# Microcontroller.net
KiCad netlist of a schematic drawn in Altium Designer
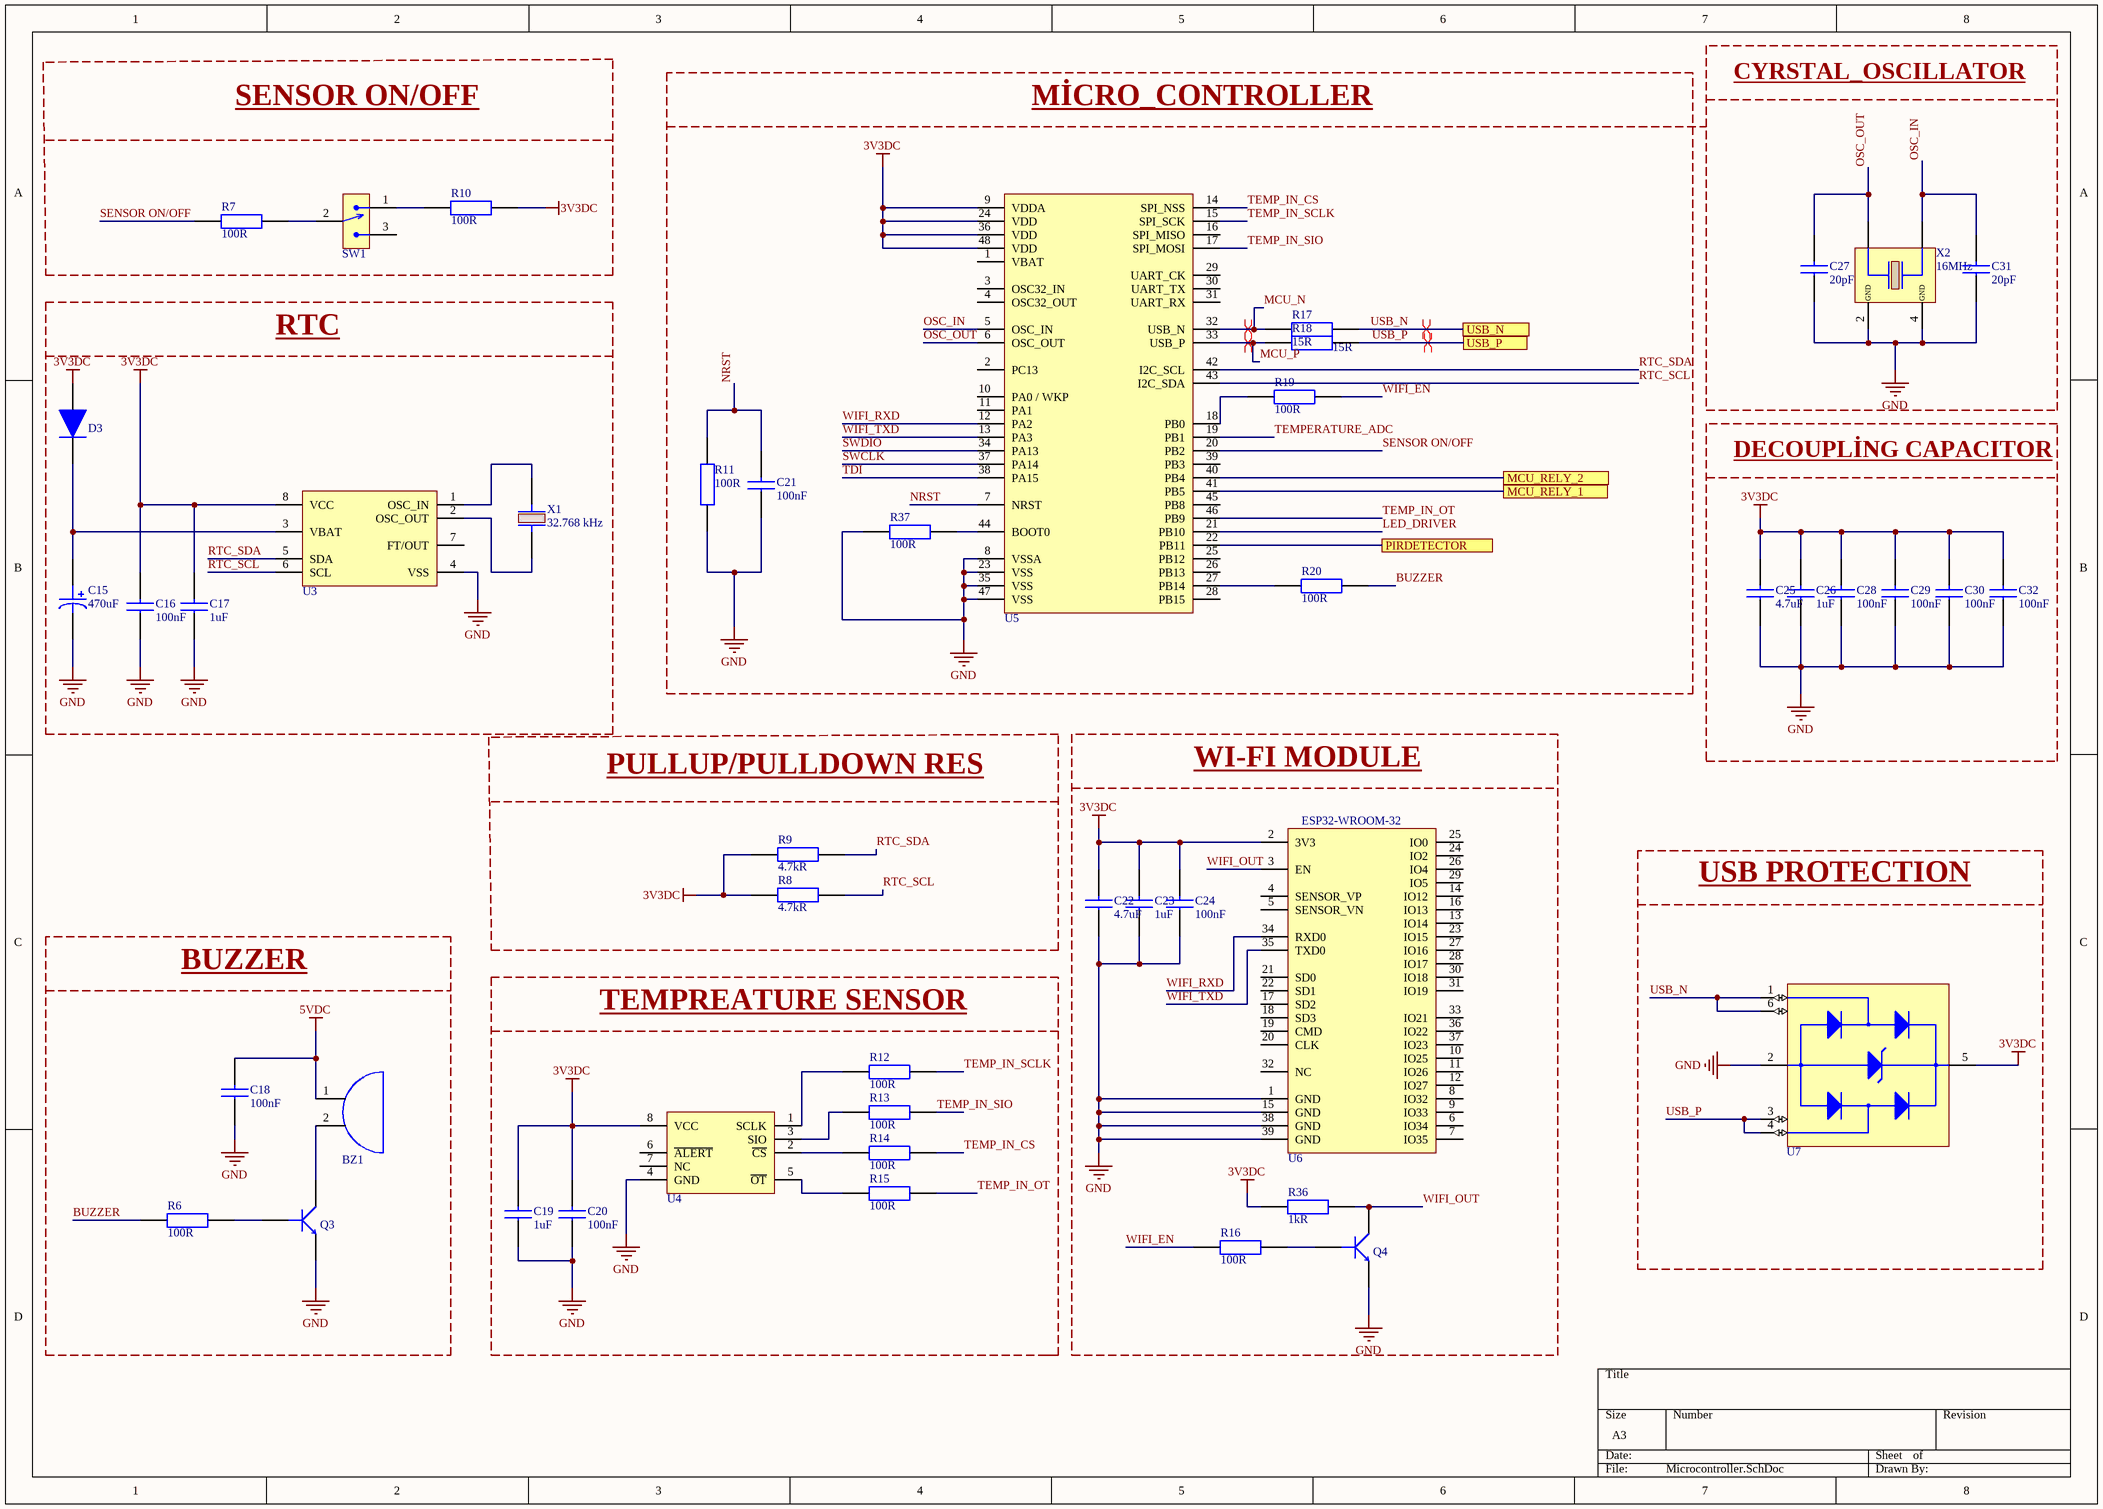
[diagram p0: Microcontroller.SchDoc]

(export (version "E")
  (design (tool "Eeschema 10.0.6"))
  (components
    (comp (ref "BZ1")
      (value "CMI-9605IC-0580T")
      (footprint "CMI-9605IC")
      (description "Buzzers Indicator, Internally Driven Magnetic 5V 30mA 2.7kHz 80dB @ 5V, 10cm Through Hole PC Pins")
      (fields (field (name "MANUFACTURER") "CUI Devices") (field (name "DESIGNED BY") "BERK"))
      (libsource (lib "UDEMY_Library") (part "CMI-9605IC-0580T"))
    )
    (comp (ref "C15")
      (value "ESH477M050AH4AA")
      (footprint "CAP_RADIAL_D10_P5")
      (description "CAP ALU ELEC 470uF 50V RADIAL")
      (fields
        (field (name "MANUFACTURER") "KEMET")
        (field (name "TOLERANCE") "20%")
        (field (name "CAPACITANCE") "470uF")
        (field (name "DESIGNED BY") "BERK")
      )
      (libsource (lib "UDEMY_Library") (part "CAP ALU ELEC 470uF 50V"))
    )
    (comp (ref "C16")
      (value "C0603C104K5RACTU")
      (footprint "CAP_0603")
      (description "CAP CER 100nF %10 0603 SMD")
      (fields
        (field (name "MANUFACTURER") "KEMET")
        (field (name "TOLERANCE") "10%")
        (field (name "CAPACITANCE") "100nF")
        (field (name "DESIGNED BY") "BERK")
      )
      (libsource (lib "UDEMY_Library") (part "CAP CER 100nF 0603"))
    )
    (comp (ref "C17")
      (value "CL21B105KBFNNNE")
      (footprint "CAP_0805")
      (description "CAP CER 1uF %10 0805")
      (fields
        (field (name "MANUFACTURER") "Samsung")
        (field (name "TOLERANCE") "10%")
        (field (name "CAPACITANCE") "1uF")
        (field (name "DESIGNED BY") "BERK")
      )
      (libsource (lib "UDEMY_Library") (part "CAP CER 1uF 0805"))
    )
    (comp (ref "C18")
      (value "C0603C104K5RACTU")
      (footprint "CAP_0603")
      (description "CAP CER 100nF %10 0603 SMD")
      (fields
        (field (name "MANUFACTURER") "KEMET")
        (field (name "TOLERANCE") "10%")
        (field (name "CAPACITANCE") "100nF")
        (field (name "DESIGNED BY") "BERK")
      )
      (libsource (lib "UDEMY_Library") (part "CAP CER 100nF 0603"))
    )
    (comp (ref "C19")
      (value "CL21B105KBFNNNE")
      (footprint "CAP_0805")
      (description "CAP CER 1uF %10 0805")
      (fields
        (field (name "MANUFACTURER") "Samsung")
        (field (name "TOLERANCE") "10%")
        (field (name "CAPACITANCE") "1uF")
        (field (name "DESIGNED BY") "BERK")
      )
      (libsource (lib "UDEMY_Library") (part "CAP CER 1uF 0805"))
    )
    (comp (ref "C20")
      (value "C0603C104K5RACTU")
      (footprint "CAP_0603")
      (description "CAP CER 100nF %10 0603 SMD")
      (fields
        (field (name "MANUFACTURER") "KEMET")
        (field (name "TOLERANCE") "10%")
        (field (name "CAPACITANCE") "100nF")
        (field (name "DESIGNED BY") "BERK")
      )
      (libsource (lib "UDEMY_Library") (part "CAP CER 100nF 0603"))
    )
    (comp (ref "C21")
      (value "C0603C104K5RACTU")
      (footprint "CAP_0603")
      (description "CAP CER 100nF %10 0603 SMD")
      (fields
        (field (name "MANUFACTURER") "KEMET")
        (field (name "TOLERANCE") "10%")
        (field (name "CAPACITANCE") "100nF")
        (field (name "DESIGNED BY") "BERK")
      )
      (libsource (lib "UDEMY_Library") (part "CAP CER 100nF 0603"))
    )
    (comp (ref "C22")
      (value "CL21A475KAQNNNE")
      (footprint "CAP_0805")
      (description "CAP CER 4.7uF %10 0805")
      (fields
        (field (name "MANUFACTURER") "Samsung")
        (field (name "TOLERANCE") "10%")
        (field (name "CAPACITANCE") "4.7uF")
        (field (name "DESIGNED BY") "BERK")
      )
      (libsource (lib "UDEMY_Library") (part "CAP CER 4.7uF 0805"))
    )
    (comp (ref "C23")
      (value "CL21B105KBFNNNE")
      (footprint "CAP_0805")
      (description "CAP CER 1uF %10 0805")
      (fields
        (field (name "MANUFACTURER") "Samsung")
        (field (name "TOLERANCE") "10%")
        (field (name "CAPACITANCE") "1uF")
        (field (name "DESIGNED BY") "BERK")
      )
      (libsource (lib "UDEMY_Library") (part "CAP CER 1uF 0805"))
    )
    (comp (ref "C24")
      (value "C0603C104K5RACTU")
      (footprint "CAP_0603")
      (description "CAP CER 100nF %10 0603 SMD")
      (fields
        (field (name "MANUFACTURER") "KEMET")
        (field (name "TOLERANCE") "10%")
        (field (name "CAPACITANCE") "100nF")
        (field (name "DESIGNED BY") "BERK")
      )
      (libsource (lib "UDEMY_Library") (part "CAP CER 100nF 0603"))
    )
    (comp (ref "C25")
      (value "CL21A475KAQNNNE")
      (footprint "CAP_0805")
      (description "CAP CER 4.7uF %10 0805")
      (fields
        (field (name "MANUFACTURER") "Samsung")
        (field (name "TOLERANCE") "10%")
        (field (name "CAPACITANCE") "4.7uF")
        (field (name "DESIGNED BY") "BERK")
      )
      (libsource (lib "UDEMY_Library") (part "CAP CER 4.7uF 0805"))
    )
    (comp (ref "C26")
      (value "CL21B105KBFNNNE")
      (footprint "CAP_0805")
      (description "CAP CER 1uF %10 0805")
      (fields
        (field (name "MANUFACTURER") "Samsung")
        (field (name "TOLERANCE") "10%")
        (field (name "CAPACITANCE") "1uF")
        (field (name "DESIGNED BY") "BERK")
      )
      (libsource (lib "UDEMY_Library") (part "CAP CER 1uF 0805"))
    )
    (comp (ref "C27")
      (value "CL10C200JB8NNNC")
      (footprint "CAP_0603")
      (description "CAP CER 20pF %5 0603 SMD")
      (fields
        (field (name "MANUFACTURER") "Samsung")
        (field (name "TOLERANCE") "5%")
        (field (name "CAPACITANCE") "20pF")
        (field (name "DESIGNED BY") "BERK")
      )
      (libsource (lib "UDEMY_Library") (part "CAP CER 20pF 0603"))
    )
    (comp (ref "C28")
      (value "C0603C104K5RACTU")
      (footprint "CAP_0603")
      (description "CAP CER 100nF %10 0603 SMD")
      (fields
        (field (name "MANUFACTURER") "KEMET")
        (field (name "TOLERANCE") "10%")
        (field (name "CAPACITANCE") "100nF")
        (field (name "DESIGNED BY") "BERK")
      )
      (libsource (lib "UDEMY_Library") (part "CAP CER 100nF 0603"))
    )
    (comp (ref "C29")
      (value "C0603C104K5RACTU")
      (footprint "CAP_0603")
      (description "CAP CER 100nF %10 0603 SMD")
      (fields
        (field (name "MANUFACTURER") "KEMET")
        (field (name "TOLERANCE") "10%")
        (field (name "CAPACITANCE") "100nF")
        (field (name "DESIGNED BY") "BERK")
      )
      (libsource (lib "UDEMY_Library") (part "CAP CER 100nF 0603"))
    )
    (comp (ref "C30")
      (value "C0603C104K5RACTU")
      (footprint "CAP_0603")
      (description "CAP CER 100nF %10 0603 SMD")
      (fields
        (field (name "MANUFACTURER") "KEMET")
        (field (name "TOLERANCE") "10%")
        (field (name "CAPACITANCE") "100nF")
        (field (name "DESIGNED BY") "BERK")
      )
      (libsource (lib "UDEMY_Library") (part "CAP CER 100nF 0603"))
    )
    (comp (ref "C31")
      (value "CL10C200JB8NNNC")
      (footprint "CAP_0603")
      (description "CAP CER 20pF %5 0603 SMD")
      (fields
        (field (name "MANUFACTURER") "Samsung")
        (field (name "TOLERANCE") "5%")
        (field (name "CAPACITANCE") "20pF")
        (field (name "DESIGNED BY") "BERK")
      )
      (libsource (lib "UDEMY_Library") (part "CAP CER 20pF 0603"))
    )
    (comp (ref "C32")
      (value "C0603C104K5RACTU")
      (footprint "CAP_0603")
      (description "CAP CER 100nF %10 0603 SMD")
      (fields
        (field (name "MANUFACTURER") "KEMET")
        (field (name "TOLERANCE") "10%")
        (field (name "CAPACITANCE") "100nF")
        (field (name "DESIGNED BY") "BERK")
      )
      (libsource (lib "UDEMY_Library") (part "CAP CER 100nF 0603"))
    )
    (comp (ref "D3")
      (value "1N4148WS")
      (footprint "SOD323F")
      (description "Diode, Single, 75 V, 150 mA, 1 V, 4 ns")
      (fields
        (field (name "MANUFACTURER") "ON Semiconductor / Fairchild")
        (field (name "DESIGNED BY") "BERK")
      )
      (libsource (lib "UDEMY_Library") (part "1N4148WS"))
    )
    (comp (ref "Q3")
      (value "MMBT3904-7-F")
      (footprint "SOT-23F")
      (description "Transistor General Purpose BJT NPN 40 Volt 0.2A Automotive 3-Pin SOT-23")
      (fields (field (name "MANUFACTURER") "Diodes Zetex") (field (name "DESIGNED BY") "BERK"))
      (libsource (lib "UDEMY_Library") (part "MMBT3904-7-F"))
    )
    (comp (ref "Q4")
      (value "MMBT3904-7-F")
      (footprint "SOT-23F")
      (description "Transistor General Purpose BJT NPN 40 Volt 0.2A Automotive 3-Pin SOT-23")
      (fields (field (name "MANUFACTURER") "Diodes Zetex") (field (name "DESIGNED BY") "BERK"))
      (libsource (lib "UDEMY_Library") (part "MMBT3904-7-F"))
    )
    (comp (ref "R6")
      (value "RC0603JR-07100RL")
      (footprint "RES_0603")
      (description "RES 100 %5 OHM 0603 SMD")
      (fields
        (field (name "MANUFACTURER") "Yageo")
        (field (name "TOLERANCE") "5%")
        (field (name "RESISTANCE") "100R")
        (field (name "DESIGNED BY") "BERK")
      )
      (libsource (lib "UDEMY_Library") (part "RES 100 OHM 0603"))
    )
    (comp (ref "R7")
      (value "RC0603JR-07100RL")
      (footprint "RES_0603")
      (description "RES 100 %5 OHM 0603 SMD")
      (fields
        (field (name "MANUFACTURER") "Yageo")
        (field (name "TOLERANCE") "5%")
        (field (name "RESISTANCE") "100R")
        (field (name "DESIGNED BY") "BERK")
      )
      (libsource (lib "UDEMY_Library") (part "RES 100 OHM 0603"))
    )
    (comp (ref "R8")
      (value "RC0603JR-074K7L")
      (footprint "RES_0603")
      (description "RES 4K7 %5 OHM 0603 SMD")
      (fields
        (field (name "MANUFACTURER") "Yageo")
        (field (name "TOLERANCE") "5%")
        (field (name "RESISTANCE") "4.7kR")
        (field (name "DESIGNED BY") "BERK")
      )
      (libsource (lib "UDEMY_Library") (part "RES 4K7 OHM 0603"))
    )
    (comp (ref "R9")
      (value "RC0603JR-074K7L")
      (footprint "RES_0603")
      (description "RES 4K7 %5 OHM 0603 SMD")
      (fields
        (field (name "MANUFACTURER") "Yageo")
        (field (name "TOLERANCE") "5%")
        (field (name "RESISTANCE") "4.7kR")
        (field (name "DESIGNED BY") "BERK")
      )
      (libsource (lib "UDEMY_Library") (part "RES 4K7 OHM 0603"))
    )
    (comp (ref "R10")
      (value "RC0603JR-07100RL")
      (footprint "RES_0603")
      (description "RES 100 %5 OHM 0603 SMD")
      (fields
        (field (name "MANUFACTURER") "Yageo")
        (field (name "TOLERANCE") "5%")
        (field (name "RESISTANCE") "100R")
        (field (name "DESIGNED BY") "BERK")
      )
      (libsource (lib "UDEMY_Library") (part "RES 100 OHM 0603"))
    )
    (comp (ref "R11")
      (value "RC0603JR-07100RL")
      (footprint "RES_0603")
      (description "RES 100 %5 OHM 0603 SMD")
      (fields
        (field (name "MANUFACTURER") "Yageo")
        (field (name "TOLERANCE") "5%")
        (field (name "RESISTANCE") "100R")
        (field (name "DESIGNED BY") "BERK")
      )
      (libsource (lib "") (part "RES 100 OHM 0603_1"))
    )
    (comp (ref "R12")
      (value "RC0603JR-07100RL")
      (footprint "RES_0603")
      (description "RES 100 %5 OHM 0603 SMD")
      (fields
        (field (name "MANUFACTURER") "Yageo")
        (field (name "TOLERANCE") "5%")
        (field (name "RESISTANCE") "100R")
        (field (name "DESIGNED BY") "BERK")
      )
      (libsource (lib "UDEMY_Library") (part "RES 100 OHM 0603"))
    )
    (comp (ref "R13")
      (value "RC0603JR-07100RL")
      (footprint "RES_0603")
      (description "RES 100 %5 OHM 0603 SMD")
      (fields
        (field (name "MANUFACTURER") "Yageo")
        (field (name "TOLERANCE") "5%")
        (field (name "RESISTANCE") "100R")
        (field (name "DESIGNED BY") "BERK")
      )
      (libsource (lib "UDEMY_Library") (part "RES 100 OHM 0603"))
    )
    (comp (ref "R14")
      (value "RC0603JR-07100RL")
      (footprint "RES_0603")
      (description "RES 100 %5 OHM 0603 SMD")
      (fields
        (field (name "MANUFACTURER") "Yageo")
        (field (name "TOLERANCE") "5%")
        (field (name "RESISTANCE") "100R")
        (field (name "DESIGNED BY") "BERK")
      )
      (libsource (lib "UDEMY_Library") (part "RES 100 OHM 0603"))
    )
    (comp (ref "R15")
      (value "RC0603JR-07100RL")
      (footprint "RES_0603")
      (description "RES 100 %5 OHM 0603 SMD")
      (fields
        (field (name "MANUFACTURER") "Yageo")
        (field (name "TOLERANCE") "5%")
        (field (name "RESISTANCE") "100R")
        (field (name "DESIGNED BY") "BERK")
      )
      (libsource (lib "UDEMY_Library") (part "RES 100 OHM 0603"))
    )
    (comp (ref "R16")
      (value "RC0603JR-07100RL")
      (footprint "RES_0603")
      (description "RES 100 %5 OHM 0603 SMD")
      (fields
        (field (name "MANUFACTURER") "Yageo")
        (field (name "TOLERANCE") "5%")
        (field (name "RESISTANCE") "100R")
        (field (name "DESIGNED BY") "BERK")
      )
      (libsource (lib "UDEMY_Library") (part "RES 100 OHM 0603"))
    )
    (comp (ref "R17")
      (value "RC0603JR-0715RL")
      (footprint "RES_0603")
      (description "RES 15 %5 OHM 0603 SMD")
      (fields
        (field (name "MANUFACTURER") "Yageo")
        (field (name "TOLERANCE") "5%")
        (field (name "RESISTANCE") "15R")
        (field (name "DESIGNED BY") "BERK")
      )
      (libsource (lib "UDEMY_Library") (part "RES 15 OHM 0603"))
    )
    (comp (ref "R18")
      (value "RC0603JR-0715RL")
      (footprint "RES_0603")
      (description "RES 15 %5 OHM 0603 SMD")
      (fields
        (field (name "MANUFACTURER") "Yageo")
        (field (name "TOLERANCE") "5%")
        (field (name "RESISTANCE") "15R")
        (field (name "DESIGNED BY") "BERK")
      )
      (libsource (lib "UDEMY_Library") (part "RES 15 OHM 0603"))
    )
    (comp (ref "R19")
      (value "RC0603JR-07100RL")
      (footprint "RES_0603")
      (description "RES 100 %5 OHM 0603 SMD")
      (fields
        (field (name "MANUFACTURER") "Yageo")
        (field (name "TOLERANCE") "5%")
        (field (name "RESISTANCE") "100R")
        (field (name "DESIGNED BY") "BERK")
      )
      (libsource (lib "UDEMY_Library") (part "RES 100 OHM 0603"))
    )
    (comp (ref "R20")
      (value "RC0603JR-07100RL")
      (footprint "RES_0603")
      (description "RES 100 %5 OHM 0603 SMD")
      (fields
        (field (name "MANUFACTURER") "Yageo")
        (field (name "TOLERANCE") "5%")
        (field (name "RESISTANCE") "100R")
        (field (name "DESIGNED BY") "BERK")
      )
      (libsource (lib "UDEMY_Library") (part "RES 100 OHM 0603"))
    )
    (comp (ref "R36")
      (value "RC0603FR-0710KL")
      (footprint "RES_0603")
      (description "RES 1K %1 OHM 0603 SMD")
      (fields
        (field (name "MANUFACTURER") "Yageo")
        (field (name "MANUFACTURER PART NUMBER") "RC0603JR-071KL")
        (field (name "RESISTANCE") "1kR")
        (field (name "DESIGNED BY") "BERK")
      )
      (libsource (lib "UDEMY_Library") (part "RES 1K OHM 0603"))
    )
    (comp (ref "R37")
      (value "RC0603JR-07100RL")
      (footprint "RES_0603")
      (description "RES 100 %5 OHM 0603 SMD")
      (fields
        (field (name "MANUFACTURER") "Yageo")
        (field (name "TOLERANCE") "5%")
        (field (name "RESISTANCE") "100R")
        (field (name "DESIGNED BY") "BERK")
      )
      (libsource (lib "UDEMY_Library") (part "RES 100 OHM 0603"))
    )
    (comp (ref "SW1")
      (value "EG1215AA")
      (footprint "EG1215AA")
      (description "Slide Switch, SPDT, 0.025A, 24V, SMD")
      (fields
        (field (name "MANUFACTURER") "E-Switch")
        (field (name "TOLERANCE") "4.95%")
        (field (name "DESIGNED BY") "BERK")
      )
      (libsource (lib "UDEMY_Library") (part "EG1215AA"))
    )
    (comp (ref "U3")
      (value "M41T00M6F")
      (footprint "SOIC8")
      (description "IC RTC CLK/CALENDAR I2C 8-SOIC")
      (fields (field (name "MANUFACTURER") "STMicroelectronics") (field (name "DESIGNED BY") "BERK"))
      (libsource (lib "UDEMY_Library") (part "M41T00M6F"))
    )
    (comp (ref "U4")
      (value "MAX6662")
      (footprint "SOIC8")
      (description "SENSOR TEMPERATURE SPI 8SOIC")
      (fields
        (field (name "MANUFACTURER") "Maxim")
        (field (name "MANUFACTURER PART NUMBER") "MAX6662MSA+")
        (field (name "DESIGNED BY") "BERK")
      )
      (libsource (lib "UDEMY_Library") (part "MAX6662"))
    )
    (comp (ref "U5")
      (value "STM32F103C6T6A")
      (footprint "LQFP-48")
      (description "MCU 32-bit STM32F ARM Cortex M3 RISC 32KB Flash 2.5V/3.3V 48-Pin LQFP Tray")
      (fields (field (name "MANUFACTURER") "STMicroelectronics") (field (name "DESIGNED BY") "BERK"))
      (libsource (lib "UDEMY_Library") (part "STM32F103C6T6A"))
    )
    (comp (ref "U6")
      (value "ESP32-WROOM-32")
      (footprint "ESP32-32")
      (description "SMD MODULE, ESP32-D0WDQ6, 32MBIT")
      (fields (field (name "MANUFACTURER") "Espressif Systems") (field (name "DESIGNED BY") "BERK"))
      (libsource (lib "UDEMY_Library") (part "ESP32-WROOM-32"))
    )
    (comp (ref "U7")
      (value "USBLC6-2SC6")
      (footprint "SOT23-6L")
      (description "TVS DIODE 5.25V 17V SOT23-6")
      (fields (field (name "MANUFACTURER") "STMicroelectronics") (field (name "DESIGNED BY") "BERK"))
      (libsource (lib "UDEMY_Library") (part "USB PROTECTION"))
    )
    (comp (ref "X1")
      (value "ABS05-32.768KHZ-T")
      (footprint "ABS05")
      (description "Crystal, 32.768 kHz, SMD, 1.6mm x 1mm, 12.5 pF, 20 ppm, ABS05 Series")
      (fields
        (field (name "MANUFACTURER") "Abracon")
        (field (name "TOLERANCE") "20ppm")
        (field (name "OPERATING FREQUENCY") "32.768 kHz")
        (field (name "DESIGNED BY") "BERK")
      )
      (libsource (lib "UDEMY_Library") (part "CRYSTAL 32768kHZ"))
    )
    (comp (ref "X2")
      (value "ECS-160-20-30B-TR")
      (footprint "ECS")
      (description "CRYSTAL 16.0000MHZ 20PF SMD")
      (fields
        (field (name "MANUFACTURER") "ECS International")
        (field (name "TOLERANCE") "50ppm")
        (field (name "FREQUENCY") "16MHz")
        (field (name "DESIGNED BY") "BERK")
      )
      (libsource (lib "UDEMY_Library") (part "CRYSTAL 16MHz"))
    )
  )
  (nets
    (net (code "2") (name "/BUZZER") (class "Default")
      (node (ref "R20") (pin "2") (pinfunction "2_2") (pintype "passive"))
      (node (ref "R6") (pin "1") (pinfunction "1_1") (pintype "passive"))
    )
    (net (code "3") (name "/LED_DRIVER") (class "Default")
      (node (ref "U5") (pin "21") (pinfunction "PB10_21") (pintype "passive"))
    )
    (net (code "4") (name "/MCU_N") (class "Default")
      (node (ref "R17") (pin "1") (pinfunction "1_1") (pintype "passive"))
      (node (ref "U5") (pin "32") (pinfunction "USB_N_32") (pintype "passive"))
    )
    (net (code "5") (name "/MCU_P") (class "Default")
      (node (ref "R18") (pin "1") (pinfunction "1_1") (pintype "passive"))
      (node (ref "U5") (pin "33") (pinfunction "USB_P_33") (pintype "passive"))
    )
    (net (code "6") (name "/MCU_RELY_1") (class "Default")
      (node (ref "U5") (pin "41") (pinfunction "PB5_41") (pintype "passive"))
    )
    (net (code "7") (name "/MCU_RELY_2") (class "Default")
      (node (ref "U5") (pin "40") (pinfunction "PB4_40") (pintype "passive"))
    )
    (net (code "8") (name "/NRST") (class "Default")
      (node (ref "C21") (pin "2") (pinfunction "2_2") (pintype "passive"))
      (node (ref "R11") (pin "2") (pinfunction "2_2") (pintype "passive"))
      (node (ref "U5") (pin "7") (pinfunction "NRST_7") (pintype "passive"))
    )
    (net (code "9") (name "/OSC_IN") (class "Default")
      (node (ref "C31") (pin "2") (pinfunction "2_2") (pintype "passive"))
      (node (ref "U5") (pin "5") (pinfunction "OSC_IN_5") (pintype "passive"))
      (node (ref "X2") (pin "3") (pinfunction "3_3") (pintype "passive"))
    )
    (net (code "10") (name "/OSC_OUT") (class "Default")
      (node (ref "C27") (pin "2") (pinfunction "2_2") (pintype "passive"))
      (node (ref "U5") (pin "6") (pinfunction "OSC_OUT_6") (pintype "passive"))
      (node (ref "X2") (pin "1") (pinfunction "1_1") (pintype "passive"))
    )
    (net (code "11") (name "/PIRDETECTOR") (class "Default")
      (node (ref "U5") (pin "22") (pinfunction "PB11_22") (pintype "passive"))
    )
    (net (code "12") (name "/RTC_SCL") (class "Default")
      (node (ref "R8") (pin "1") (pinfunction "1_1") (pintype "passive"))
      (node (ref "U3") (pin "6") (pinfunction "SCL_6") (pintype "passive"))
      (node (ref "U5") (pin "43") (pinfunction "I2C_SDA_43") (pintype "passive"))
    )
    (net (code "13") (name "/RTC_SDA") (class "Default")
      (node (ref "R9") (pin "1") (pinfunction "1_1") (pintype "passive"))
      (node (ref "U3") (pin "5") (pinfunction "SDA_5") (pintype "passive"))
      (node (ref "U5") (pin "42") (pinfunction "I2C_SCL_42") (pintype "passive"))
    )
    (net (code "14") (name "/SENSOR ON{slash}OFF") (class "Default")
      (node (ref "R7") (pin "1") (pinfunction "1_1") (pintype "passive"))
      (node (ref "U5") (pin "20") (pinfunction "PB2_20") (pintype "passive"))
    )
    (net (code "15") (name "/SWCLK") (class "Default")
      (node (ref "U5") (pin "37") (pinfunction "PA14_37") (pintype "passive"))
    )
    (net (code "16") (name "/SWDIO") (class "Default")
      (node (ref "U5") (pin "34") (pinfunction "PA13_34") (pintype "passive"))
    )
    (net (code "17") (name "/TDI") (class "Default")
      (node (ref "U5") (pin "38") (pinfunction "PA15_38") (pintype "passive"))
    )
    (net (code "18") (name "/TEMPERATURE_ADC") (class "Default")
      (node (ref "U5") (pin "19") (pinfunction "PB1_19") (pintype "passive"))
    )
    (net (code "19") (name "/TEMP_IN_CS") (class "Default")
      (node (ref "R14") (pin "2") (pinfunction "2_2") (pintype "passive"))
      (node (ref "U5") (pin "14") (pinfunction "SPI_NSS_14") (pintype "passive"))
    )
    (net (code "20") (name "/TEMP_IN_OT") (class "Default")
      (node (ref "R15") (pin "2") (pinfunction "2_2") (pintype "passive"))
      (node (ref "U5") (pin "46") (pinfunction "PB9_46") (pintype "passive"))
    )
    (net (code "21") (name "/TEMP_IN_SCLK") (class "Default")
      (node (ref "R12") (pin "2") (pinfunction "2_2") (pintype "passive"))
      (node (ref "U5") (pin "15") (pinfunction "SPI_SCK_15") (pintype "passive"))
    )
    (net (code "22") (name "/TEMP_IN_SIO") (class "Default")
      (node (ref "R13") (pin "2") (pinfunction "2_2") (pintype "passive"))
      (node (ref "U5") (pin "17") (pinfunction "SPI_MOSI_17") (pintype "passive"))
    )
    (net (code "23") (name "/USB_N") (class "Default")
      (node (ref "R17") (pin "2") (pinfunction "2_2") (pintype "passive"))
      (node (ref "U7") (pin "1") (pinfunction "I/O1_1") (pintype "bidirectional"))
      (node (ref "U7") (pin "6") (pinfunction "I/O1_6") (pintype "bidirectional"))
    )
    (net (code "24") (name "/USB_P") (class "Default")
      (node (ref "R18") (pin "2") (pinfunction "2_2") (pintype "passive"))
      (node (ref "U7") (pin "3") (pinfunction "I/O2_3") (pintype "bidirectional"))
      (node (ref "U7") (pin "4") (pinfunction "I/O2_4") (pintype "bidirectional"))
    )
    (net (code "25") (name "/WIFI_EN") (class "Default")
      (node (ref "R16") (pin "1") (pinfunction "1_1") (pintype "passive"))
      (node (ref "R19") (pin "2") (pinfunction "2_2") (pintype "passive"))
    )
    (net (code "26") (name "/WIFI_OUT") (class "Default")
      (node (ref "Q4") (pin "3") (pinfunction "C_3") (pintype "power_in"))
      (node (ref "R36") (pin "2") (pinfunction "2_2") (pintype "passive"))
      (node (ref "U6") (pin "3") (pinfunction "EN_3") (pintype "passive"))
    )
    (net (code "27") (name "/WIFI_RXD") (class "Default")
      (node (ref "U5") (pin "12") (pinfunction "PA2_12") (pintype "passive"))
      (node (ref "U6") (pin "34") (pinfunction "RXD0_34") (pintype "passive"))
    )
    (net (code "28") (name "/WIFI_TXD") (class "Default")
      (node (ref "U5") (pin "13") (pinfunction "PA3_13") (pintype "passive"))
      (node (ref "U6") (pin "35") (pinfunction "TXD0_35") (pintype "passive"))
    )
    (net (code "29") (name "3V3DC") (class "Default")
      (node (ref "C16") (pin "2") (pinfunction "2_2") (pintype "passive"))
      (node (ref "C17") (pin "2") (pinfunction "2_2") (pintype "passive"))
      (node (ref "C19") (pin "2") (pinfunction "2_2") (pintype "passive"))
      (node (ref "C20") (pin "2") (pinfunction "2_2") (pintype "passive"))
      (node (ref "C22") (pin "2") (pinfunction "2_2") (pintype "passive"))
      (node (ref "C23") (pin "2") (pinfunction "2_2") (pintype "passive"))
      (node (ref "C24") (pin "2") (pinfunction "2_2") (pintype "passive"))
      (node (ref "C25") (pin "2") (pinfunction "2_2") (pintype "passive"))
      (node (ref "C26") (pin "2") (pinfunction "2_2") (pintype "passive"))
      (node (ref "C28") (pin "2") (pinfunction "2_2") (pintype "passive"))
      (node (ref "C29") (pin "2") (pinfunction "2_2") (pintype "passive"))
      (node (ref "C30") (pin "2") (pinfunction "2_2") (pintype "passive"))
      (node (ref "C32") (pin "2") (pinfunction "2_2") (pintype "passive"))
      (node (ref "D3") (pin "2") (pinfunction "2_2") (pintype "power_in"))
      (node (ref "R10") (pin "2") (pinfunction "2_2") (pintype "passive"))
      (node (ref "R36") (pin "1") (pinfunction "1_1") (pintype "passive"))
      (node (ref "R8") (pin "2") (pinfunction "2_2") (pintype "passive"))
      (node (ref "R9") (pin "2") (pinfunction "2_2") (pintype "passive"))
      (node (ref "U3") (pin "8") (pinfunction "VCC_8") (pintype "passive"))
      (node (ref "U4") (pin "8") (pinfunction "VCC_8") (pintype "passive"))
      (node (ref "U5") (pin "24") (pinfunction "VDD_24") (pintype "passive"))
      (node (ref "U5") (pin "36") (pinfunction "VDD_36") (pintype "passive"))
      (node (ref "U5") (pin "48") (pinfunction "VDD_48") (pintype "passive"))
      (node (ref "U5") (pin "9") (pinfunction "VDDA_9") (pintype "passive"))
      (node (ref "U6") (pin "2") (pinfunction "3V3_2") (pintype "passive"))
      (node (ref "U7") (pin "5") (pinfunction "VBUS_5") (pintype "power_in"))
    )
    (net (code "30") (name "5VDC") (class "Default")
      (node (ref "BZ1") (pin "1") (pinfunction "1_1") (pintype "passive"))
      (node (ref "C18") (pin "2") (pinfunction "2_2") (pintype "passive"))
    )
    (net (code "31") (name "GND") (class "Default")
      (node (ref "C15") (pin "2") (pinfunction "2_2") (pintype "passive"))
      (node (ref "C16") (pin "1") (pinfunction "1_1") (pintype "passive"))
      (node (ref "C17") (pin "1") (pinfunction "1_1") (pintype "passive"))
      (node (ref "C18") (pin "1") (pinfunction "1_1") (pintype "passive"))
      (node (ref "C19") (pin "1") (pinfunction "1_1") (pintype "passive"))
      (node (ref "C20") (pin "1") (pinfunction "1_1") (pintype "passive"))
      (node (ref "C21") (pin "1") (pinfunction "1_1") (pintype "passive"))
      (node (ref "C22") (pin "1") (pinfunction "1_1") (pintype "passive"))
      (node (ref "C23") (pin "1") (pinfunction "1_1") (pintype "passive"))
      (node (ref "C24") (pin "1") (pinfunction "1_1") (pintype "passive"))
      (node (ref "C25") (pin "1") (pinfunction "1_1") (pintype "passive"))
      (node (ref "C26") (pin "1") (pinfunction "1_1") (pintype "passive"))
      (node (ref "C27") (pin "1") (pinfunction "1_1") (pintype "passive"))
      (node (ref "C28") (pin "1") (pinfunction "1_1") (pintype "passive"))
      (node (ref "C29") (pin "1") (pinfunction "1_1") (pintype "passive"))
      (node (ref "C30") (pin "1") (pinfunction "1_1") (pintype "passive"))
      (node (ref "C31") (pin "1") (pinfunction "1_1") (pintype "passive"))
      (node (ref "C32") (pin "1") (pinfunction "1_1") (pintype "passive"))
      (node (ref "Q3") (pin "2") (pinfunction "E_2") (pintype "power_in"))
      (node (ref "Q4") (pin "2") (pinfunction "E_2") (pintype "power_in"))
      (node (ref "R11") (pin "1") (pinfunction "1_1") (pintype "passive"))
      (node (ref "R37") (pin "1") (pinfunction "1_1") (pintype "passive"))
      (node (ref "U3") (pin "4") (pinfunction "VSS_4") (pintype "passive"))
      (node (ref "U4") (pin "4") (pinfunction "GND_4") (pintype "passive"))
      (node (ref "U5") (pin "23") (pinfunction "VSS_23") (pintype "passive"))
      (node (ref "U5") (pin "35") (pinfunction "VSS_35") (pintype "passive"))
      (node (ref "U5") (pin "47") (pinfunction "VSS_47") (pintype "passive"))
      (node (ref "U5") (pin "8") (pinfunction "VSSA_8") (pintype "passive"))
      (node (ref "U6") (pin "1") (pinfunction "GND_1") (pintype "passive"))
      (node (ref "U6") (pin "15") (pinfunction "GND_15") (pintype "passive"))
      (node (ref "U6") (pin "38") (pinfunction "GND_38") (pintype "passive"))
      (node (ref "U6") (pin "39") (pinfunction "GND_39") (pintype "passive"))
      (node (ref "U7") (pin "2") (pinfunction "GND_2") (pintype "power_in"))
      (node (ref "X2") (pin "2") (pinfunction "GND_2") (pintype "passive"))
      (node (ref "X2") (pin "4") (pinfunction "GND_4") (pintype "passive"))
    )
    (net (code "32") (name "Net-(Q3-B)") (class "Default")
      (node (ref "Q3") (pin "1") (pinfunction "B_1") (pintype "power_in"))
      (node (ref "R6") (pin "2") (pinfunction "2_2") (pintype "passive"))
    )
    (net (code "33") (name "Net-(Q3-C)") (class "Default")
      (node (ref "BZ1") (pin "2") (pinfunction "2_2") (pintype "passive"))
      (node (ref "Q3") (pin "3") (pinfunction "C_3") (pintype "power_in"))
    )
    (net (code "34") (name "Net-(Q4-B)") (class "Default")
      (node (ref "Q4") (pin "1") (pinfunction "B_1") (pintype "power_in"))
      (node (ref "R16") (pin "2") (pinfunction "2_2") (pintype "passive"))
    )
    (net (code "35") (name "Net-(R7-Pad2)") (class "Default")
      (node (ref "R7") (pin "2") (pinfunction "2_2") (pintype "passive"))
      (node (ref "SW1") (pin "2") (pinfunction "2_2") (pintype "passive"))
    )
    (net (code "36") (name "Net-(R10-Pad1)") (class "Default")
      (node (ref "R10") (pin "1") (pinfunction "1_1") (pintype "passive"))
      (node (ref "SW1") (pin "1") (pinfunction "1_1") (pintype "passive"))
    )
    (net (code "37") (name "Net-(U3-OSC_IN)") (class "Default")
      (node (ref "U3") (pin "1") (pinfunction "OSC_IN_1") (pintype "passive"))
      (node (ref "X1") (pin "2") (pinfunction "2_2") (pintype "passive"))
    )
    (net (code "38") (name "Net-(U3-OSC_OUT)") (class "Default")
      (node (ref "U3") (pin "2") (pinfunction "OSC_OUT_2") (pintype "passive"))
      (node (ref "X1") (pin "1") (pinfunction "1_1") (pintype "passive"))
    )
    (net (code "39") (name "Net-(U3-VBAT)") (class "Default")
      (node (ref "C15") (pin "1") (pinfunction "1_1") (pintype "passive"))
      (node (ref "D3") (pin "1") (pinfunction "1_1") (pintype "power_in"))
      (node (ref "U3") (pin "3") (pinfunction "VBAT_3") (pintype "passive"))
    )
    (net (code "40") (name "Net-(U4-SCLK)") (class "Default")
      (node (ref "R12") (pin "1") (pinfunction "1_1") (pintype "passive"))
      (node (ref "U4") (pin "1") (pinfunction "SCLK_1") (pintype "passive"))
    )
    (net (code "41") (name "Net-(U4-SIO)") (class "Default")
      (node (ref "R13") (pin "1") (pinfunction "1_1") (pintype "passive"))
      (node (ref "U4") (pin "3") (pinfunction "SIO_3") (pintype "passive"))
    )
    (net (code "42") (name "Net-(U4-~{CS})") (class "Default")
      (node (ref "R14") (pin "1") (pinfunction "1_1") (pintype "passive"))
      (node (ref "U4") (pin "2") (pinfunction "~{CS}_2") (pintype "passive"))
    )
    (net (code "43") (name "Net-(U4-~{OT})") (class "Default")
      (node (ref "R15") (pin "1") (pinfunction "1_1") (pintype "passive"))
      (node (ref "U4") (pin "5") (pinfunction "~{OT}_5") (pintype "passive"))
    )
    (net (code "44") (name "Net-(U5-BOOT0)") (class "Default")
      (node (ref "R37") (pin "2") (pinfunction "2_2") (pintype "passive"))
      (node (ref "U5") (pin "44") (pinfunction "BOOT0_44") (pintype "passive"))
    )
    (net (code "45") (name "Net-(U5-PB0)") (class "Default")
      (node (ref "R19") (pin "1") (pinfunction "1_1") (pintype "passive"))
      (node (ref "U5") (pin "18") (pinfunction "PB0_18") (pintype "passive"))
    )
    (net (code "46") (name "Net-(U5-PB14)") (class "Default")
      (node (ref "R20") (pin "1") (pinfunction "1_1") (pintype "passive"))
      (node (ref "U5") (pin "27") (pinfunction "PB14_27") (pintype "passive"))
    )
    (net (code "47") (name "unconnected-(SW1-Pad3)") (class "Default")
      (node (ref "SW1") (pin "3") (pinfunction "3_3") (pintype "passive"))
    )
    (net (code "48") (name "unconnected-(U3-FT{slash}OUT-Pad7)") (class "Default")
      (node (ref "U3") (pin "7") (pinfunction "FT/OUT_7") (pintype "passive"))
    )
    (net (code "49") (name "unconnected-(U4-NC-Pad7)") (class "Default")
      (node (ref "U4") (pin "7") (pinfunction "NC_7") (pintype "passive"))
    )
    (net (code "50") (name "unconnected-(U4-~{ALERT}-Pad6)") (class "Default")
      (node (ref "U4") (pin "6") (pinfunction "~{ALERT}_6") (pintype "passive"))
    )
    (net (code "51") (name "unconnected-(U5-OSC32_IN-Pad3)") (class "Default")
      (node (ref "U5") (pin "3") (pinfunction "OSC32_IN_3") (pintype "passive"))
    )
    (net (code "52") (name "unconnected-(U5-OSC32_OUT-Pad4)") (class "Default")
      (node (ref "U5") (pin "4") (pinfunction "OSC32_OUT_4") (pintype "passive"))
    )
    (net (code "53") (name "unconnected-(U5-PA0_{slash}_WKP-Pad10)") (class "Default")
      (node (ref "U5") (pin "10") (pinfunction "PA0_/_WKP_10") (pintype "passive"))
    )
    (net (code "54") (name "unconnected-(U5-PA1-Pad11)") (class "Default")
      (node (ref "U5") (pin "11") (pinfunction "PA1_11") (pintype "passive"))
    )
    (net (code "55") (name "unconnected-(U5-PB3-Pad39)") (class "Default")
      (node (ref "U5") (pin "39") (pinfunction "PB3_39") (pintype "passive"))
    )
    (net (code "56") (name "unconnected-(U5-PB8-Pad45)") (class "Default")
      (node (ref "U5") (pin "45") (pinfunction "PB8_45") (pintype "passive"))
    )
    (net (code "57") (name "unconnected-(U5-PB12-Pad25)") (class "Default")
      (node (ref "U5") (pin "25") (pinfunction "PB12_25") (pintype "passive"))
    )
    (net (code "58") (name "unconnected-(U5-PB13-Pad26)") (class "Default")
      (node (ref "U5") (pin "26") (pinfunction "PB13_26") (pintype "passive"))
    )
    (net (code "59") (name "unconnected-(U5-PB15-Pad28)") (class "Default")
      (node (ref "U5") (pin "28") (pinfunction "PB15_28") (pintype "passive"))
    )
    (net (code "60") (name "unconnected-(U5-PC13-Pad2)") (class "Default")
      (node (ref "U5") (pin "2") (pinfunction "PC13_2") (pintype "passive"))
    )
    (net (code "61") (name "unconnected-(U5-SPI_MISO-Pad16)") (class "Default")
      (node (ref "U5") (pin "16") (pinfunction "SPI_MISO_16") (pintype "passive"))
    )
    (net (code "62") (name "unconnected-(U5-UART_CK-Pad29)") (class "Default")
      (node (ref "U5") (pin "29") (pinfunction "UART_CK_29") (pintype "passive"))
    )
    (net (code "63") (name "unconnected-(U5-UART_RX-Pad31)") (class "Default")
      (node (ref "U5") (pin "31") (pinfunction "UART_RX_31") (pintype "passive"))
    )
    (net (code "64") (name "unconnected-(U5-UART_TX-Pad30)") (class "Default")
      (node (ref "U5") (pin "30") (pinfunction "UART_TX_30") (pintype "passive"))
    )
    (net (code "65") (name "unconnected-(U5-VBAT-Pad1)") (class "Default")
      (node (ref "U5") (pin "1") (pinfunction "VBAT_1") (pintype "passive"))
    )
    (net (code "66") (name "unconnected-(U6-CLK-Pad20)") (class "Default")
      (node (ref "U6") (pin "20") (pinfunction "CLK_20") (pintype "passive"))
    )
    (net (code "67") (name "unconnected-(U6-CMD-Pad19)") (class "Default")
      (node (ref "U6") (pin "19") (pinfunction "CMD_19") (pintype "passive"))
    )
    (net (code "68") (name "unconnected-(U6-IO0-Pad25)") (class "Default")
      (node (ref "U6") (pin "25") (pinfunction "IO0_25") (pintype "passive"))
    )
    (net (code "69") (name "unconnected-(U6-IO2-Pad24)") (class "Default")
      (node (ref "U6") (pin "24") (pinfunction "IO2_24") (pintype "passive"))
    )
    (net (code "70") (name "unconnected-(U6-IO4-Pad26)") (class "Default")
      (node (ref "U6") (pin "26") (pinfunction "IO4_26") (pintype "passive"))
    )
    (net (code "71") (name "unconnected-(U6-IO5-Pad29)") (class "Default")
      (node (ref "U6") (pin "29") (pinfunction "IO5_29") (pintype "passive"))
    )
    (net (code "72") (name "unconnected-(U6-IO12-Pad14)") (class "Default")
      (node (ref "U6") (pin "14") (pinfunction "IO12_14") (pintype "passive"))
    )
    (net (code "73") (name "unconnected-(U6-IO13-Pad16)") (class "Default")
      (node (ref "U6") (pin "16") (pinfunction "IO13_16") (pintype "passive"))
    )
    (net (code "74") (name "unconnected-(U6-IO14-Pad13)") (class "Default")
      (node (ref "U6") (pin "13") (pinfunction "IO14_13") (pintype "passive"))
    )
    (net (code "75") (name "unconnected-(U6-IO15-Pad23)") (class "Default")
      (node (ref "U6") (pin "23") (pinfunction "IO15_23") (pintype "passive"))
    )
    (net (code "76") (name "unconnected-(U6-IO16-Pad27)") (class "Default")
      (node (ref "U6") (pin "27") (pinfunction "IO16_27") (pintype "passive"))
    )
    (net (code "77") (name "unconnected-(U6-IO17-Pad28)") (class "Default")
      (node (ref "U6") (pin "28") (pinfunction "IO17_28") (pintype "passive"))
    )
    (net (code "78") (name "unconnected-(U6-IO18-Pad30)") (class "Default")
      (node (ref "U6") (pin "30") (pinfunction "IO18_30") (pintype "passive"))
    )
    (net (code "79") (name "unconnected-(U6-IO19-Pad31)") (class "Default")
      (node (ref "U6") (pin "31") (pinfunction "IO19_31") (pintype "passive"))
    )
    (net (code "80") (name "unconnected-(U6-IO21-Pad33)") (class "Default")
      (node (ref "U6") (pin "33") (pinfunction "IO21_33") (pintype "passive"))
    )
    (net (code "81") (name "unconnected-(U6-IO22-Pad36)") (class "Default")
      (node (ref "U6") (pin "36") (pinfunction "IO22_36") (pintype "passive"))
    )
    (net (code "82") (name "unconnected-(U6-IO23-Pad37)") (class "Default")
      (node (ref "U6") (pin "37") (pinfunction "IO23_37") (pintype "passive"))
    )
    (net (code "83") (name "unconnected-(U6-IO25-Pad10)") (class "Default")
      (node (ref "U6") (pin "10") (pinfunction "IO25_10") (pintype "passive"))
    )
    (net (code "84") (name "unconnected-(U6-IO26-Pad11)") (class "Default")
      (node (ref "U6") (pin "11") (pinfunction "IO26_11") (pintype "passive"))
    )
    (net (code "85") (name "unconnected-(U6-IO27-Pad12)") (class "Default")
      (node (ref "U6") (pin "12") (pinfunction "IO27_12") (pintype "passive"))
    )
    (net (code "86") (name "unconnected-(U6-IO32-Pad8)") (class "Default")
      (node (ref "U6") (pin "8") (pinfunction "IO32_8") (pintype "passive"))
    )
    (net (code "87") (name "unconnected-(U6-IO33-Pad9)") (class "Default")
      (node (ref "U6") (pin "9") (pinfunction "IO33_9") (pintype "passive"))
    )
    (net (code "88") (name "unconnected-(U6-IO34-Pad6)") (class "Default")
      (node (ref "U6") (pin "6") (pinfunction "IO34_6") (pintype "passive"))
    )
    (net (code "89") (name "unconnected-(U6-IO35-Pad7)") (class "Default")
      (node (ref "U6") (pin "7") (pinfunction "IO35_7") (pintype "passive"))
    )
    (net (code "90") (name "unconnected-(U6-NC-Pad32)") (class "Default")
      (node (ref "U6") (pin "32") (pinfunction "NC_32") (pintype "passive"))
    )
    (net (code "91") (name "unconnected-(U6-SD0-Pad21)") (class "Default")
      (node (ref "U6") (pin "21") (pinfunction "SD0_21") (pintype "passive"))
    )
    (net (code "92") (name "unconnected-(U6-SD1-Pad22)") (class "Default")
      (node (ref "U6") (pin "22") (pinfunction "SD1_22") (pintype "passive"))
    )
    (net (code "93") (name "unconnected-(U6-SD2-Pad17)") (class "Default")
      (node (ref "U6") (pin "17") (pinfunction "SD2_17") (pintype "passive"))
    )
    (net (code "94") (name "unconnected-(U6-SD3-Pad18)") (class "Default")
      (node (ref "U6") (pin "18") (pinfunction "SD3_18") (pintype "passive"))
    )
    (net (code "95") (name "unconnected-(U6-SENSOR_VN-Pad5)") (class "Default")
      (node (ref "U6") (pin "5") (pinfunction "SENSOR_VN_5") (pintype "passive"))
    )
    (net (code "96") (name "unconnected-(U6-SENSOR_VP-Pad4)") (class "Default")
      (node (ref "U6") (pin "4") (pinfunction "SENSOR_VP_4") (pintype "passive"))
    )
  )
)
